# RelayDelayNo7Seg.net
KiCad netlist of a schematic drawn in EAGLE
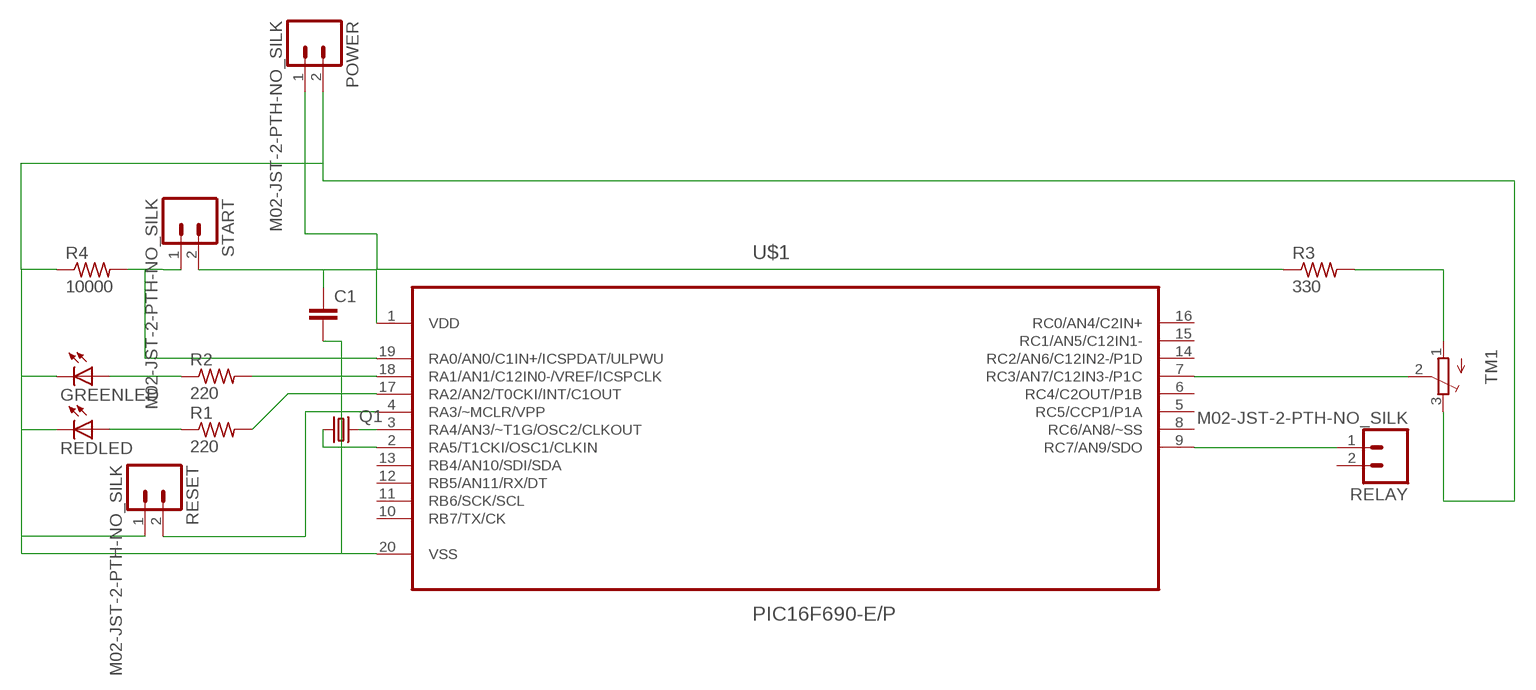
[diagram p0: schematic, sheet 1]

(export (version "E")
  (design (tool "Eeschema 10.0.6"))
  (components
    (comp (ref "C1")
      (value "CAPEZ")
      (footprint "eagle-import:CAP-PTH-SMALLEZ")
      (libsource (lib "eagle-import") (part "CAPEZ"))
    )
    (comp (ref "GREENLED")
      (value "LED5MM")
      (footprint "eagle-import:LED5MM")
      (libsource (lib "eagle-import") (part "LED5MM"))
    )
    (comp (ref "POWER")
      (value "M02-JST-2-PTH-NO_SILK")
      (footprint "eagle-import:JST-2-PTH-NS")
      (libsource (lib "eagle-import") (part "M02-JST-2-PTH-NO_SILK"))
    )
    (comp (ref "Q1")
      (value "CRYSTALHC49S")
      (footprint "eagle-import:HC49_S")
      (libsource (lib "eagle-import") (part "CRYSTALHC49S"))
    )
    (comp (ref "R1")
      (value "220")
      (footprint "eagle-import:0204V")
      (libsource (lib "eagle-import") (part "R-US_0204/2V"))
    )
    (comp (ref "R2")
      (value "220")
      (footprint "eagle-import:0204V")
      (libsource (lib "eagle-import") (part "R-US_0204/2V"))
    )
    (comp (ref "R3")
      (value "330")
      (footprint "eagle-import:0204V")
      (libsource (lib "eagle-import") (part "R-US_0204/2V"))
    )
    (comp (ref "R4")
      (value "10000")
      (footprint "eagle-import:0204V")
      (libsource (lib "eagle-import") (part "R-US_0204/2V"))
    )
    (comp (ref "REDLED")
      (value "LED5MM")
      (footprint "eagle-import:LED5MM")
      (libsource (lib "eagle-import") (part "LED5MM"))
    )
    (comp (ref "RELAY")
      (value "M02-JST-2-PTH-NO_SILK")
      (footprint "eagle-import:JST-2-PTH-NS")
      (libsource (lib "eagle-import") (part "M02-JST-2-PTH-NO_SILK"))
    )
    (comp (ref "RESET")
      (value "M02-JST-2-PTH-NO_SILK")
      (footprint "eagle-import:JST-2-PTH-NS")
      (libsource (lib "eagle-import") (part "M02-JST-2-PTH-NO_SILK"))
    )
    (comp (ref "START")
      (value "M02-JST-2-PTH-NO_SILK")
      (footprint "eagle-import:JST-2-PTH-NS")
      (libsource (lib "eagle-import") (part "M02-JST-2-PTH-NO_SILK"))
    )
    (comp (ref "TM1")
      (value "TRIMPOT3386")
      (footprint "eagle-import:TRIM-3386")
      (libsource (lib "eagle-import") (part "TRIMPOT3386"))
    )
    (comp (ref "U$1")
      (value "PIC16F690-E/P")
      (footprint "eagle-import:DIP254P762X533-20")
      (libsource (lib "eagle-import") (part "PIC16F690-E/P"))
    )
  )
  (nets
    (net (code "1") (name "Net-(GREENLED-C)") (class "Default")
      (node (ref "C1") (pin "2") (pinfunction "2_2") (pintype "passive"))
      (node (ref "GREENLED") (pin "K") (pinfunction "C_K") (pintype "passive"))
      (node (ref "POWER") (pin "2") (pinfunction "2_2") (pintype "passive"))
      (node (ref "R4") (pin "1") (pinfunction "1_1") (pintype "passive"))
      (node (ref "REDLED") (pin "K") (pinfunction "C_K") (pintype "passive"))
      (node (ref "RESET") (pin "1") (pinfunction "1_1") (pintype "passive"))
      (node (ref "TM1") (pin "3") (pinfunction "E_3") (pintype "passive"))
      (node (ref "U$1") (pin "20") (pinfunction "VSS_20") (pintype "power_in"))
    )
    (net (code "2") (name "Net-(GREENLED-PadA)") (class "Default")
      (node (ref "GREENLED") (pin "A") (pinfunction "A_A") (pintype "passive"))
      (node (ref "R2") (pin "1") (pinfunction "1_1") (pintype "passive"))
    )
    (net (code "3") (name "Net-(R1-Pad1)") (class "Default")
      (node (ref "R1") (pin "1") (pinfunction "1_1") (pintype "passive"))
      (node (ref "REDLED") (pin "A") (pinfunction "A_A") (pintype "passive"))
    )
    (net (code "4") (name "Net-(TM1-A)") (class "Default")
      (node (ref "R3") (pin "2") (pinfunction "2_2") (pintype "passive"))
      (node (ref "TM1") (pin "1") (pinfunction "A_1") (pintype "passive"))
    )
    (net (code "5") (name "Net-(TM1-S)") (class "Default")
      (node (ref "TM1") (pin "2") (pinfunction "S_2") (pintype "passive"))
      (node (ref "U$1") (pin "7") (pinfunction "RC3/AN7/C12IN3-/P1C_7") (pintype "bidirectional"))
    )
    (net (code "6") (name "Net-(U$1-RA0{slash}AN0{slash}C1IN+{slash}ICSPDAT{slash}ULPWU)") (class "Default")
      (node (ref "R4") (pin "2") (pinfunction "2_2") (pintype "passive"))
      (node (ref "START") (pin "1") (pinfunction "1_1") (pintype "passive"))
      (node (ref "U$1") (pin "19") (pinfunction "RA0/AN0/C1IN+/ICSPDAT/ULPWU_19") (pintype "bidirectional"))
    )
    (net (code "7") (name "Net-(U$1-RA1{slash}AN1{slash}C12IN0-{slash}VREF{slash}ICSPCLK)") (class "Default")
      (node (ref "R2") (pin "2") (pinfunction "2_2") (pintype "passive"))
      (node (ref "U$1") (pin "18") (pinfunction "RA1/AN1/C12IN0-/VREF/ICSPCLK_18") (pintype "bidirectional"))
    )
    (net (code "8") (name "Net-(U$1-RA2{slash}AN2{slash}T0CKI{slash}INT{slash}C1OUT)") (class "Default")
      (node (ref "R1") (pin "2") (pinfunction "2_2") (pintype "passive"))
      (node (ref "U$1") (pin "17") (pinfunction "RA2/AN2/T0CKI/INT/C1OUT_17") (pintype "bidirectional"))
    )
    (net (code "9") (name "Net-(U$1-RA3{slash}~{MCLR{slash}VPP})") (class "Default")
      (node (ref "RESET") (pin "2") (pinfunction "2_2") (pintype "passive"))
      (node (ref "U$1") (pin "4") (pinfunction "RA3/~{MCLR/VPP}_4") (pintype "input"))
    )
    (net (code "10") (name "Net-(U$1-RA4{slash}AN3{slash}~{T1G{slash}OSC2{slash}CLKOUT})") (class "Default")
      (node (ref "Q1") (pin "2") (pinfunction "2_2") (pintype "passive"))
      (node (ref "U$1") (pin "3") (pinfunction "RA4/AN3/~{T1G/OSC2/CLKOUT}_3") (pintype "bidirectional"))
    )
    (net (code "11") (name "Net-(U$1-RA5{slash}T1CKI{slash}OSC1{slash}CLKIN)") (class "Default")
      (node (ref "Q1") (pin "1") (pinfunction "1_1") (pintype "passive"))
      (node (ref "U$1") (pin "2") (pinfunction "RA5/T1CKI/OSC1/CLKIN_2") (pintype "bidirectional"))
    )
    (net (code "12") (name "Net-(U$1-RC7{slash}AN9{slash}SDO)") (class "Default")
      (node (ref "RELAY") (pin "1") (pinfunction "1_1") (pintype "passive"))
      (node (ref "U$1") (pin "9") (pinfunction "RC7/AN9/SDO_9") (pintype "bidirectional"))
    )
    (net (code "13") (name "Net-(U$1-VDD)") (class "Default")
      (node (ref "C1") (pin "1") (pinfunction "1_1") (pintype "passive"))
      (node (ref "POWER") (pin "1") (pinfunction "1_1") (pintype "passive"))
      (node (ref "R3") (pin "1") (pinfunction "1_1") (pintype "passive"))
      (node (ref "START") (pin "2") (pinfunction "2_2") (pintype "passive"))
      (node (ref "U$1") (pin "1") (pinfunction "VDD_1") (pintype "power_in"))
    )
    (net (code "14") (name "unconnected-(RELAY-Pad2)") (class "Default")
      (node (ref "RELAY") (pin "2") (pinfunction "2_2") (pintype "passive"))
    )
    (net (code "15") (name "unconnected-(U$1-RB4{slash}AN10{slash}SDI{slash}SDA-Pad13)") (class "Default")
      (node (ref "U$1") (pin "13") (pinfunction "RB4/AN10/SDI/SDA_13") (pintype "bidirectional"))
    )
    (net (code "16") (name "unconnected-(U$1-RB5{slash}AN11{slash}RX{slash}DT-Pad12)") (class "Default")
      (node (ref "U$1") (pin "12") (pinfunction "RB5/AN11/RX/DT_12") (pintype "bidirectional"))
    )
    (net (code "17") (name "unconnected-(U$1-RB6{slash}SCK{slash}SCL-Pad11)") (class "Default")
      (node (ref "U$1") (pin "11") (pinfunction "RB6/SCK/SCL_11") (pintype "bidirectional"))
    )
    (net (code "18") (name "unconnected-(U$1-RB7{slash}TX{slash}CK-Pad10)") (class "Default")
      (node (ref "U$1") (pin "10") (pinfunction "RB7/TX/CK_10") (pintype "bidirectional"))
    )
    (net (code "19") (name "unconnected-(U$1-RC0{slash}AN4{slash}C2IN+-Pad16)") (class "Default")
      (node (ref "U$1") (pin "16") (pinfunction "RC0/AN4/C2IN+_16") (pintype "bidirectional"))
    )
    (net (code "20") (name "unconnected-(U$1-RC1{slash}AN5{slash}C12IN1--Pad15)") (class "Default")
      (node (ref "U$1") (pin "15") (pinfunction "RC1/AN5/C12IN1-_15") (pintype "bidirectional"))
    )
    (net (code "21") (name "unconnected-(U$1-RC2{slash}AN6{slash}C12IN2-{slash}P1D-Pad14)") (class "Default")
      (node (ref "U$1") (pin "14") (pinfunction "RC2/AN6/C12IN2-/P1D_14") (pintype "bidirectional"))
    )
    (net (code "22") (name "unconnected-(U$1-RC4{slash}C2OUT{slash}P1B-Pad6)") (class "Default")
      (node (ref "U$1") (pin "6") (pinfunction "RC4/C2OUT/P1B_6") (pintype "bidirectional"))
    )
    (net (code "23") (name "unconnected-(U$1-RC5{slash}CCP1{slash}P1A-Pad5)") (class "Default")
      (node (ref "U$1") (pin "5") (pinfunction "RC5/CCP1/P1A_5") (pintype "bidirectional"))
    )
    (net (code "24") (name "unconnected-(U$1-RC6{slash}AN8{slash}~{SS}-Pad8)") (class "Default")
      (node (ref "U$1") (pin "8") (pinfunction "RC6/AN8/~{SS}_8") (pintype "bidirectional"))
    )
  )
)
